# PocketKerbal.net
KiCad netlist of a schematic drawn in EAGLE
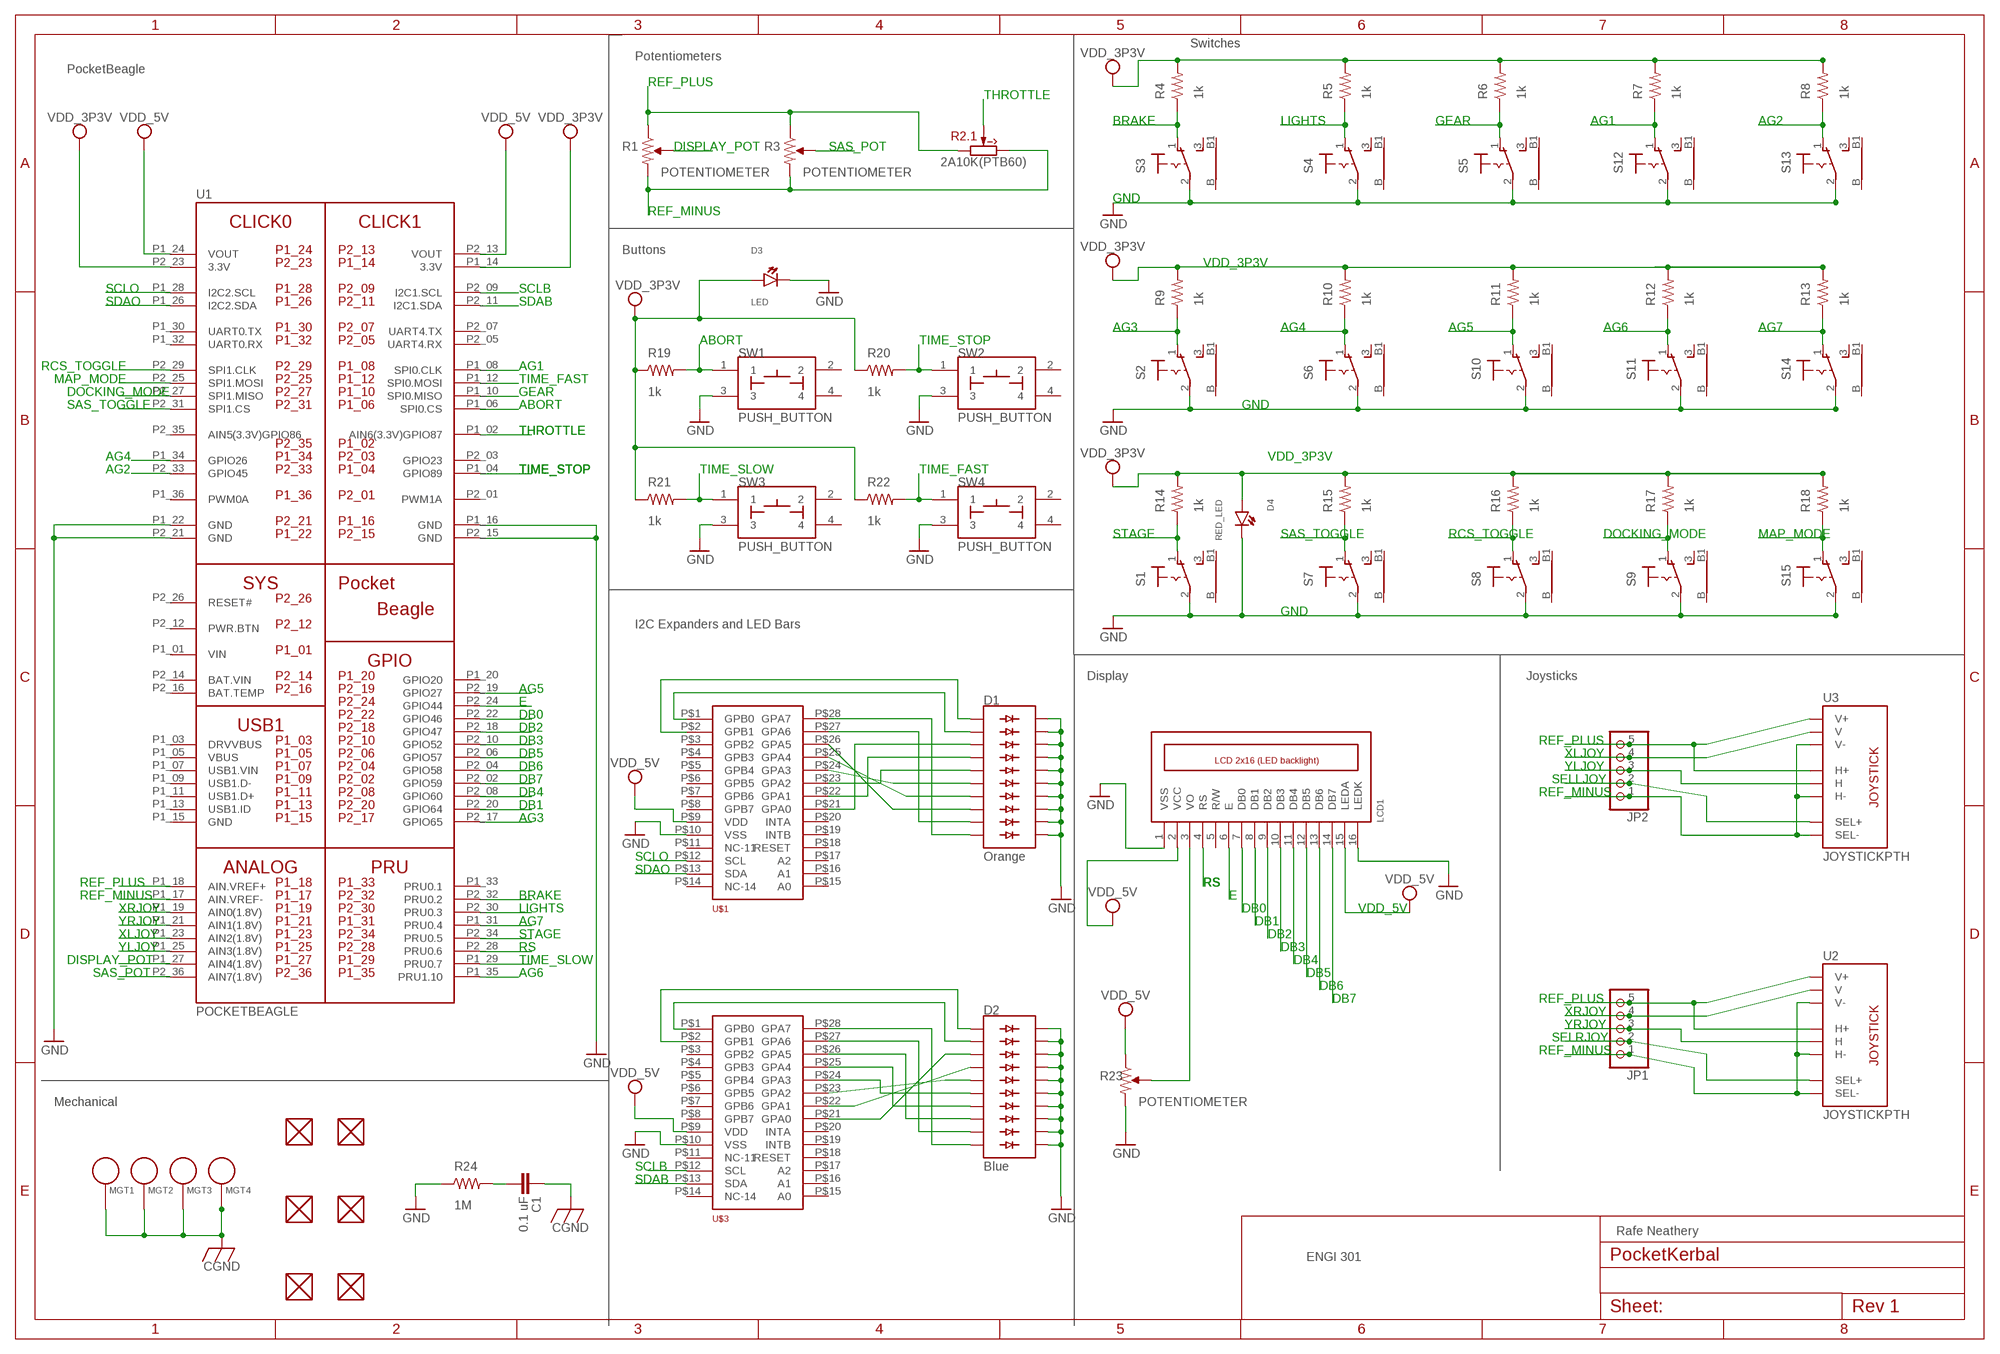
[diagram p0: schematic, sheet 1]

(export (version "E")
  (design (tool "Eeschema 10.0.6"))
  (components
    (comp (ref "C1")
      (value "0.1 uF")
      (footprint "eagle-import:C0402")
      (libsource (lib "eagle-import") (part "C_C0402"))
    )
    (comp (ref "D1")
      (value "RED")
      (footprint "eagle-import:LED_BARGRAPH_10")
      (libsource (lib "eagle-import") (part "LED_BARGRAPH_10RED"))
    )
    (comp (ref "D2")
      (value "RED")
      (footprint "eagle-import:LED_BARGRAPH_10")
      (libsource (lib "eagle-import") (part "LED_BARGRAPH_10RED"))
    )
    (comp (ref "D3")
      (value "LED")
      (footprint "eagle-import:EIA-STD")
      (libsource (lib "eagle-import") (part "LED"))
    )
    (comp (ref "D4")
      (value "RED_LED")
      (footprint "eagle-import:EIA-STD")
      (libsource (lib "eagle-import") (part "LED"))
    )
    (comp (ref "FUD1")
      (value "FIDUCIAL")
      (footprint "eagle-import:FIDUCIAL_40MIL")
      (libsource (lib "eagle-import") (part "FIDUCIAL"))
    )
    (comp (ref "FUD2")
      (value "FIDUCIAL")
      (footprint "eagle-import:FIDUCIAL_40MIL")
      (libsource (lib "eagle-import") (part "FIDUCIAL"))
    )
    (comp (ref "FUD5")
      (value "FIDUCIAL")
      (footprint "eagle-import:FIDUCIAL_40MIL")
      (libsource (lib "eagle-import") (part "FIDUCIAL"))
    )
    (comp (ref "FUD6")
      (value "FIDUCIAL")
      (footprint "eagle-import:FIDUCIAL_40MIL")
      (libsource (lib "eagle-import") (part "FIDUCIAL"))
    )
    (comp (ref "FUD9")
      (value "FIDUCIAL")
      (footprint "eagle-import:FIDUCIAL_40MIL")
      (libsource (lib "eagle-import") (part "FIDUCIAL"))
    )
    (comp (ref "FUD10")
      (value "FIDUCIAL")
      (footprint "eagle-import:FIDUCIAL_40MIL")
      (libsource (lib "eagle-import") (part "FIDUCIAL"))
    )
    (comp (ref "JP1")
      (value "PINHD-1X5")
      (footprint "eagle-import:1X05")
      (libsource (lib "eagle-import") (part "PINHD-1X5"))
    )
    (comp (ref "JP2")
      (value "PINHD-1X5")
      (footprint "eagle-import:1X05")
      (libsource (lib "eagle-import") (part "PINHD-1X5"))
    )
    (comp (ref "LCD1")
      (value "LCD_2X16_SIL")
      (footprint "eagle-import:HY-1602F")
      (libsource (lib "eagle-import") (part "LCD_2X16_SIL"))
    )
    (comp (ref "MGT1")
      (value "MOUNTING_HOLE")
      (footprint "eagle-import:MOUNTING_HOLE")
      (libsource (lib "eagle-import") (part "MOUNTING_HOLE"))
    )
    (comp (ref "MGT2")
      (value "MOUNTING_HOLE")
      (footprint "eagle-import:MOUNTING_HOLE")
      (libsource (lib "eagle-import") (part "MOUNTING_HOLE"))
    )
    (comp (ref "MGT3")
      (value "MOUNTING_HOLE")
      (footprint "eagle-import:MOUNTING_HOLE")
      (libsource (lib "eagle-import") (part "MOUNTING_HOLE"))
    )
    (comp (ref "MGT4")
      (value "MOUNTING_HOLE")
      (footprint "eagle-import:MOUNTING_HOLE")
      (libsource (lib "eagle-import") (part "MOUNTING_HOLE"))
    )
    (comp (ref "R1")
      (value "POTENTIOMETER")
      (footprint "eagle-import:POT-PO90S")
      (libsource (lib "eagle-import") (part "POTENTIOMETER"))
    )
    (comp (ref "R2")
      (value "2A10K(PTB60)")
      (footprint "eagle-import:PTB6044")
      (libsource (lib "eagle-import") (part "2?(PTB60)A10K"))
    )
    (comp (ref "R3")
      (value "POTENTIOMETER")
      (footprint "eagle-import:POT-PO90S")
      (libsource (lib "eagle-import") (part "POTENTIOMETER"))
    )
    (comp (ref "R4")
      (value "1k")
      (footprint "eagle-import:R0603")
      (libsource (lib "eagle-import") (part "R_R0603"))
    )
    (comp (ref "R5")
      (value "1k")
      (footprint "eagle-import:R0603")
      (libsource (lib "eagle-import") (part "R_R0603"))
    )
    (comp (ref "R6")
      (value "1k")
      (footprint "eagle-import:R0603")
      (libsource (lib "eagle-import") (part "R_R0603"))
    )
    (comp (ref "R7")
      (value "1k")
      (footprint "eagle-import:R0603")
      (libsource (lib "eagle-import") (part "R_R0603"))
    )
    (comp (ref "R8")
      (value "1k")
      (footprint "eagle-import:R0603")
      (libsource (lib "eagle-import") (part "R_R0603"))
    )
    (comp (ref "R9")
      (value "1k")
      (footprint "eagle-import:R0603")
      (libsource (lib "eagle-import") (part "R_R0603"))
    )
    (comp (ref "R10")
      (value "1k")
      (footprint "eagle-import:R0603")
      (libsource (lib "eagle-import") (part "R_R0603"))
    )
    (comp (ref "R11")
      (value "1k")
      (footprint "eagle-import:R0603")
      (libsource (lib "eagle-import") (part "R_R0603"))
    )
    (comp (ref "R12")
      (value "1k")
      (footprint "eagle-import:R0603")
      (libsource (lib "eagle-import") (part "R_R0603"))
    )
    (comp (ref "R13")
      (value "1k")
      (footprint "eagle-import:R0603")
      (libsource (lib "eagle-import") (part "R_R0603"))
    )
    (comp (ref "R14")
      (value "1k")
      (footprint "eagle-import:R0603")
      (libsource (lib "eagle-import") (part "R_R0603"))
    )
    (comp (ref "R15")
      (value "1k")
      (footprint "eagle-import:R0603")
      (libsource (lib "eagle-import") (part "R_R0603"))
    )
    (comp (ref "R16")
      (value "1k")
      (footprint "eagle-import:R0603")
      (libsource (lib "eagle-import") (part "R_R0603"))
    )
    (comp (ref "R17")
      (value "1k")
      (footprint "eagle-import:R0603")
      (libsource (lib "eagle-import") (part "R_R0603"))
    )
    (comp (ref "R18")
      (value "1k")
      (footprint "eagle-import:R0603")
      (libsource (lib "eagle-import") (part "R_R0603"))
    )
    (comp (ref "R19")
      (value "1k")
      (footprint "eagle-import:R0603")
      (libsource (lib "eagle-import") (part "R_R0603"))
    )
    (comp (ref "R20")
      (value "1k")
      (footprint "eagle-import:R0603")
      (libsource (lib "eagle-import") (part "R_R0603"))
    )
    (comp (ref "R21")
      (value "1k")
      (footprint "eagle-import:R0603")
      (libsource (lib "eagle-import") (part "R_R0603"))
    )
    (comp (ref "R22")
      (value "1k")
      (footprint "eagle-import:R0603")
      (libsource (lib "eagle-import") (part "R_R0603"))
    )
    (comp (ref "R23")
      (value "POTENTIOMETER")
      (footprint "eagle-import:POT-PO90S")
      (libsource (lib "eagle-import") (part "POTENTIOMETER"))
    )
    (comp (ref "R24")
      (value "1M")
      (footprint "eagle-import:R0603")
      (libsource (lib "eagle-import") (part "R_R0603"))
    )
    (comp (ref "S1")
      (value "9070-1W")
      (footprint "eagle-import:9070-1W")
      (libsource (lib "eagle-import") (part "9070-1W"))
    )
    (comp (ref "S2")
      (value "9070-1W")
      (footprint "eagle-import:9070-1W")
      (libsource (lib "eagle-import") (part "9070-1W"))
    )
    (comp (ref "S3")
      (value "9070-1W")
      (footprint "eagle-import:9070-1W")
      (libsource (lib "eagle-import") (part "9070-1W"))
    )
    (comp (ref "S4")
      (value "9070-1W")
      (footprint "eagle-import:9070-1W")
      (libsource (lib "eagle-import") (part "9070-1W"))
    )
    (comp (ref "S5")
      (value "9070-1W")
      (footprint "eagle-import:9070-1W")
      (libsource (lib "eagle-import") (part "9070-1W"))
    )
    (comp (ref "S6")
      (value "9070-1W")
      (footprint "eagle-import:9070-1W")
      (libsource (lib "eagle-import") (part "9070-1W"))
    )
    (comp (ref "S7")
      (value "9070-1W")
      (footprint "eagle-import:9070-1W")
      (libsource (lib "eagle-import") (part "9070-1W"))
    )
    (comp (ref "S8")
      (value "9070-1W")
      (footprint "eagle-import:9070-1W")
      (libsource (lib "eagle-import") (part "9070-1W"))
    )
    (comp (ref "S9")
      (value "9070-1W")
      (footprint "eagle-import:9070-1W")
      (libsource (lib "eagle-import") (part "9070-1W"))
    )
    (comp (ref "S10")
      (value "9070-1W")
      (footprint "eagle-import:9070-1W")
      (libsource (lib "eagle-import") (part "9070-1W"))
    )
    (comp (ref "S11")
      (value "9070-1W")
      (footprint "eagle-import:9070-1W")
      (libsource (lib "eagle-import") (part "9070-1W"))
    )
    (comp (ref "S12")
      (value "9070-1W")
      (footprint "eagle-import:9070-1W")
      (libsource (lib "eagle-import") (part "9070-1W"))
    )
    (comp (ref "S13")
      (value "9070-1W")
      (footprint "eagle-import:9070-1W")
      (libsource (lib "eagle-import") (part "9070-1W"))
    )
    (comp (ref "S14")
      (value "9070-1W")
      (footprint "eagle-import:9070-1W")
      (libsource (lib "eagle-import") (part "9070-1W"))
    )
    (comp (ref "S15")
      (value "9070-1W")
      (footprint "eagle-import:9070-1W")
      (libsource (lib "eagle-import") (part "9070-1W"))
    )
    (comp (ref "SW1")
      (value "PUSH_BUTTON")
      (footprint "eagle-import:BUTTON_12.5MM")
      (libsource (lib "eagle-import") (part "PUSH_BUTTON"))
    )
    (comp (ref "SW2")
      (value "PUSH_BUTTON")
      (footprint "eagle-import:BUTTON_12.5MM")
      (libsource (lib "eagle-import") (part "PUSH_BUTTON"))
    )
    (comp (ref "SW3")
      (value "PUSH_BUTTON")
      (footprint "eagle-import:BUTTON_12.5MM")
      (libsource (lib "eagle-import") (part "PUSH_BUTTON"))
    )
    (comp (ref "SW4")
      (value "PUSH_BUTTON")
      (footprint "eagle-import:BUTTON_12.5MM")
      (libsource (lib "eagle-import") (part "PUSH_BUTTON"))
    )
    (comp (ref "U$1")
      (value "MCP23017-E/SP")
      (footprint "eagle-import:DIP28")
      (libsource (lib "eagle-import") (part "MCP23017-E/SP"))
    )
    (comp (ref "U$3")
      (value "MCP23017-E/SP")
      (footprint "eagle-import:DIP28")
      (libsource (lib "eagle-import") (part "MCP23017-E/SP"))
    )
    (comp (ref "U1")
      (value "POCKETBEAGLE")
      (footprint "eagle-import:POCKETBEAGLE")
      (libsource (lib "eagle-import") (part "POCKETBEAGLE"))
    )
    (comp (ref "U2")
      (value "JOYSTICKPTH")
      (footprint "eagle-import:JOYSTICK")
      (libsource (lib "eagle-import") (part "JOYSTICKPTH"))
    )
    (comp (ref "U3")
      (value "JOYSTICKPTH")
      (footprint "eagle-import:JOYSTICK")
      (libsource (lib "eagle-import") (part "JOYSTICKPTH"))
    )
  )
  (nets
    (net (code "1") (name "/ABORT") (class "Default")
      (node (ref "R19") (pin "2") (pinfunction "2_2") (pintype "passive"))
      (node (ref "SW1") (pin "1") (pinfunction "1_1") (pintype "bidirectional"))
      (node (ref "U1") (pin "P1_06") (pinfunction "SPI0.CS_P1_06") (pintype "bidirectional"))
    )
    (net (code "2") (name "/AG1") (class "Default")
      (node (ref "R7") (pin "1") (pinfunction "1_1") (pintype "passive"))
      (node (ref "S12") (pin "1") (pinfunction "O_1") (pintype "passive"))
      (node (ref "U1") (pin "P1_08") (pinfunction "SPI0.CLK_P1_08") (pintype "bidirectional"))
    )
    (net (code "3") (name "/AG2") (class "Default")
      (node (ref "R8") (pin "1") (pinfunction "1_1") (pintype "passive"))
      (node (ref "S13") (pin "1") (pinfunction "O_1") (pintype "passive"))
      (node (ref "U1") (pin "P2_33") (pinfunction "GPIO45_P2_33") (pintype "bidirectional"))
    )
    (net (code "4") (name "/AG3") (class "Default")
      (node (ref "R9") (pin "1") (pinfunction "1_1") (pintype "passive"))
      (node (ref "S2") (pin "1") (pinfunction "O_1") (pintype "passive"))
      (node (ref "U1") (pin "P2_17") (pinfunction "GPIO65_P2_17") (pintype "bidirectional"))
    )
    (net (code "5") (name "/AG4") (class "Default")
      (node (ref "R10") (pin "1") (pinfunction "1_1") (pintype "passive"))
      (node (ref "S6") (pin "1") (pinfunction "O_1") (pintype "passive"))
      (node (ref "U1") (pin "P1_34") (pinfunction "GPIO26_P1_34") (pintype "bidirectional"))
    )
    (net (code "6") (name "/AG5") (class "Default")
      (node (ref "R11") (pin "1") (pinfunction "1_1") (pintype "passive"))
      (node (ref "S10") (pin "1") (pinfunction "O_1") (pintype "passive"))
      (node (ref "U1") (pin "P2_19") (pinfunction "GPIO27_P2_19") (pintype "bidirectional"))
    )
    (net (code "7") (name "/AG6") (class "Default")
      (node (ref "R12") (pin "1") (pinfunction "1_1") (pintype "passive"))
      (node (ref "S11") (pin "1") (pinfunction "O_1") (pintype "passive"))
      (node (ref "U1") (pin "P1_35") (pinfunction "PRU1.10_P1_35") (pintype "bidirectional"))
    )
    (net (code "8") (name "/AG7") (class "Default")
      (node (ref "R13") (pin "1") (pinfunction "1_1") (pintype "passive"))
      (node (ref "S14") (pin "1") (pinfunction "O_1") (pintype "passive"))
      (node (ref "U1") (pin "P1_31") (pinfunction "PRU0.4_P1_31") (pintype "bidirectional"))
    )
    (net (code "9") (name "/BAT.VIN") (class "Default")
      (node (ref "U1") (pin "P2_14") (pinfunction "BAT.VIN_P2_14") (pintype "power_in"))
    )
    (net (code "10") (name "/BRAKE") (class "Default")
      (node (ref "R4") (pin "1") (pinfunction "1_1") (pintype "passive"))
      (node (ref "S3") (pin "1") (pinfunction "O_1") (pintype "passive"))
      (node (ref "U1") (pin "P2_32") (pinfunction "PRU0.2_P2_32") (pintype "bidirectional"))
    )
    (net (code "11") (name "/DB0") (class "Default")
      (node (ref "LCD1") (pin "7") (pinfunction "DB0_7") (pintype "bidirectional"))
      (node (ref "U1") (pin "P2_22") (pinfunction "GPIO46_P2_22") (pintype "bidirectional"))
    )
    (net (code "12") (name "/DB1") (class "Default")
      (node (ref "LCD1") (pin "8") (pinfunction "DB1_8") (pintype "bidirectional"))
      (node (ref "U1") (pin "P2_20") (pinfunction "GPIO64_P2_20") (pintype "bidirectional"))
    )
    (net (code "13") (name "/DB2") (class "Default")
      (node (ref "LCD1") (pin "9") (pinfunction "DB2_9") (pintype "bidirectional"))
      (node (ref "U1") (pin "P2_18") (pinfunction "GPIO47_P2_18") (pintype "bidirectional"))
    )
    (net (code "14") (name "/DB3") (class "Default")
      (node (ref "LCD1") (pin "10") (pinfunction "DB3_10") (pintype "bidirectional"))
      (node (ref "U1") (pin "P2_10") (pinfunction "GPIO52_P2_10") (pintype "bidirectional"))
    )
    (net (code "15") (name "/DB4") (class "Default")
      (node (ref "LCD1") (pin "11") (pinfunction "DB4_11") (pintype "bidirectional"))
      (node (ref "U1") (pin "P2_08") (pinfunction "GPIO60_P2_08") (pintype "bidirectional"))
    )
    (net (code "16") (name "/DB5") (class "Default")
      (node (ref "LCD1") (pin "12") (pinfunction "DB5_12") (pintype "bidirectional"))
      (node (ref "U1") (pin "P2_06") (pinfunction "GPIO57_P2_06") (pintype "bidirectional"))
    )
    (net (code "17") (name "/DB6") (class "Default")
      (node (ref "LCD1") (pin "13") (pinfunction "DB6_13") (pintype "bidirectional"))
      (node (ref "U1") (pin "P2_04") (pinfunction "GPIO58_P2_04") (pintype "bidirectional"))
    )
    (net (code "18") (name "/DB7") (class "Default")
      (node (ref "LCD1") (pin "14") (pinfunction "DB7_14") (pintype "bidirectional"))
      (node (ref "U1") (pin "P2_02") (pinfunction "GPIO59_P2_02") (pintype "bidirectional"))
    )
    (net (code "19") (name "/DISPLAY_POT") (class "Default")
      (node (ref "R1") (pin "S") (pinfunction "S_S") (pintype "bidirectional"))
      (node (ref "U1") (pin "P1_27") (pinfunction "AIN4(1.8V)_P1_27") (pintype "input"))
    )
    (net (code "20") (name "/DOCKING_MODE") (class "Default")
      (node (ref "R17") (pin "1") (pinfunction "1_1") (pintype "passive"))
      (node (ref "S9") (pin "1") (pinfunction "O_1") (pintype "passive"))
      (node (ref "U1") (pin "P2_27") (pinfunction "SPI1.MISO_P2_27") (pintype "bidirectional"))
    )
    (net (code "21") (name "/E") (class "Default")
      (node (ref "LCD1") (pin "6") (pinfunction "E_6") (pintype "input"))
      (node (ref "U1") (pin "P2_24") (pinfunction "GPIO44_P2_24") (pintype "bidirectional"))
    )
    (net (code "22") (name "/GEAR") (class "Default")
      (node (ref "R6") (pin "1") (pinfunction "1_1") (pintype "passive"))
      (node (ref "S5") (pin "1") (pinfunction "O_1") (pintype "passive"))
      (node (ref "U1") (pin "P1_10") (pinfunction "SPI0.MISO_P1_10") (pintype "bidirectional"))
    )
    (net (code "23") (name "/LIGHTS") (class "Default")
      (node (ref "R5") (pin "1") (pinfunction "1_1") (pintype "passive"))
      (node (ref "S4") (pin "1") (pinfunction "O_1") (pintype "passive"))
      (node (ref "U1") (pin "P2_30") (pinfunction "PRU0.3_P2_30") (pintype "bidirectional"))
    )
    (net (code "24") (name "/MAP_MODE") (class "Default")
      (node (ref "R18") (pin "1") (pinfunction "1_1") (pintype "passive"))
      (node (ref "S15") (pin "1") (pinfunction "O_1") (pintype "passive"))
      (node (ref "U1") (pin "P2_25") (pinfunction "SPI1.MOSI_P2_25") (pintype "bidirectional"))
    )
    (net (code "25") (name "/RCS_TOGGLE") (class "Default")
      (node (ref "R16") (pin "1") (pinfunction "1_1") (pintype "passive"))
      (node (ref "S8") (pin "1") (pinfunction "O_1") (pintype "passive"))
      (node (ref "U1") (pin "P2_29") (pinfunction "SPI1.CLK_P2_29") (pintype "bidirectional"))
    )
    (net (code "26") (name "/REF_MINUS") (class "Default")
      (node (ref "JP1") (pin "1") (pinfunction "1_1") (pintype "passive"))
      (node (ref "JP2") (pin "1") (pinfunction "1_1") (pintype "passive"))
      (node (ref "R1") (pin "CW") (pinfunction "CW_CW") (pintype "passive"))
      (node (ref "R2") (pin "A3") (pinfunction "CW_A3") (pintype "passive"))
      (node (ref "R3") (pin "CW") (pinfunction "CW_CW") (pintype "passive"))
      (node (ref "U1") (pin "P1_17") (pinfunction "AIN.VREF-_P1_17") (pintype "input"))
      (node (ref "U2") (pin "B2A") (pinfunction "SEL-_B2A") (pintype "bidirectional"))
      (node (ref "U2") (pin "H3") (pinfunction "H-_H3") (pintype "bidirectional"))
      (node (ref "U2") (pin "V3") (pinfunction "V-_V3") (pintype "bidirectional"))
      (node (ref "U3") (pin "B2A") (pinfunction "SEL-_B2A") (pintype "bidirectional"))
      (node (ref "U3") (pin "H3") (pinfunction "H-_H3") (pintype "bidirectional"))
      (node (ref "U3") (pin "V3") (pinfunction "V-_V3") (pintype "bidirectional"))
    )
    (net (code "27") (name "/REF_PLUS") (class "Default")
      (node (ref "JP1") (pin "5") (pinfunction "5_5") (pintype "passive"))
      (node (ref "JP2") (pin "5") (pinfunction "5_5") (pintype "passive"))
      (node (ref "R1") (pin "CCW") (pinfunction "CCW_CCW") (pintype "passive"))
      (node (ref "R2") (pin "A1") (pinfunction "CCW_A1") (pintype "passive"))
      (node (ref "R3") (pin "CCW") (pinfunction "CCW_CCW") (pintype "passive"))
      (node (ref "U1") (pin "P1_18") (pinfunction "AIN.VREF+_P1_18") (pintype "input"))
      (node (ref "U2") (pin "H1") (pinfunction "H+_H1") (pintype "bidirectional"))
      (node (ref "U2") (pin "V1") (pinfunction "V+_V1") (pintype "bidirectional"))
      (node (ref "U3") (pin "H1") (pinfunction "H+_H1") (pintype "bidirectional"))
      (node (ref "U3") (pin "V1") (pinfunction "V+_V1") (pintype "bidirectional"))
    )
    (net (code "28") (name "/RS") (class "Default")
      (node (ref "LCD1") (pin "4") (pinfunction "RS_4") (pintype "input"))
      (node (ref "U1") (pin "P2_28") (pinfunction "PRU0.6_P2_28") (pintype "bidirectional"))
    )
    (net (code "29") (name "/SAS_POT") (class "Default")
      (node (ref "R3") (pin "S") (pinfunction "S_S") (pintype "bidirectional"))
      (node (ref "U1") (pin "P2_36") (pinfunction "AIN7(1.8V)_P2_36") (pintype "input"))
    )
    (net (code "30") (name "/SAS_TOGGLE") (class "Default")
      (node (ref "R15") (pin "1") (pinfunction "1_1") (pintype "passive"))
      (node (ref "S7") (pin "1") (pinfunction "O_1") (pintype "passive"))
      (node (ref "U1") (pin "P2_31") (pinfunction "SPI1.CS_P2_31") (pintype "bidirectional"))
    )
    (net (code "31") (name "/SCLB") (class "Default")
      (node (ref "U$3") (pin "P$12") (pinfunction "SCL_P$12") (pintype "bidirectional"))
      (node (ref "U1") (pin "P2_09") (pinfunction "I2C1.SCL_P2_09") (pintype "bidirectional"))
    )
    (net (code "32") (name "/SCLO") (class "Default")
      (node (ref "U$1") (pin "P$12") (pinfunction "SCL_P$12") (pintype "bidirectional"))
      (node (ref "U1") (pin "P1_28") (pinfunction "I2C2.SCL_P1_28") (pintype "bidirectional"))
    )
    (net (code "33") (name "/SDAB") (class "Default")
      (node (ref "U$3") (pin "P$13") (pinfunction "SDA_P$13") (pintype "bidirectional"))
      (node (ref "U1") (pin "P2_11") (pinfunction "I2C1.SDA_P2_11") (pintype "bidirectional"))
    )
    (net (code "34") (name "/SDAO") (class "Default")
      (node (ref "U$1") (pin "P$13") (pinfunction "SDA_P$13") (pintype "bidirectional"))
      (node (ref "U1") (pin "P1_26") (pinfunction "I2C2.SDA_P1_26") (pintype "bidirectional"))
    )
    (net (code "35") (name "/SELLJOY") (class "Default")
      (node (ref "JP2") (pin "2") (pinfunction "2_2") (pintype "passive"))
      (node (ref "U3") (pin "B1A") (pinfunction "SEL+_B1A") (pintype "bidirectional"))
    )
    (net (code "36") (name "/SELRJOY") (class "Default")
      (node (ref "JP1") (pin "2") (pinfunction "2_2") (pintype "passive"))
      (node (ref "U2") (pin "B1A") (pinfunction "SEL+_B1A") (pintype "bidirectional"))
    )
    (net (code "37") (name "/STAGE") (class "Default")
      (node (ref "R14") (pin "1") (pinfunction "1_1") (pintype "passive"))
      (node (ref "S1") (pin "1") (pinfunction "O_1") (pintype "passive"))
      (node (ref "U1") (pin "P2_34") (pinfunction "PRU0.5_P2_34") (pintype "bidirectional"))
    )
    (net (code "38") (name "/THROTTLE") (class "Default")
      (node (ref "R2") (pin "A2") (pinfunction "W_A2") (pintype "passive"))
      (node (ref "U1") (pin "P1_02") (pinfunction "AIN6(3.3V)GPIO87_P1_02") (pintype "bidirectional"))
    )
    (net (code "39") (name "/TIME_FAST") (class "Default")
      (node (ref "R22") (pin "2") (pinfunction "2_2") (pintype "passive"))
      (node (ref "SW4") (pin "1") (pinfunction "1_1") (pintype "bidirectional"))
      (node (ref "U1") (pin "P1_12") (pinfunction "SPI0.MOSI_P1_12") (pintype "bidirectional"))
    )
    (net (code "40") (name "/TIME_SLOW") (class "Default")
      (node (ref "R21") (pin "2") (pinfunction "2_2") (pintype "passive"))
      (node (ref "SW3") (pin "1") (pinfunction "1_1") (pintype "bidirectional"))
      (node (ref "U1") (pin "P1_29") (pinfunction "PRU0.7_P1_29") (pintype "bidirectional"))
    )
    (net (code "41") (name "/TIME_STOP") (class "Default")
      (node (ref "R20") (pin "2") (pinfunction "2_2") (pintype "passive"))
      (node (ref "SW2") (pin "1") (pinfunction "1_1") (pintype "bidirectional"))
      (node (ref "U1") (pin "P1_04") (pinfunction "GPIO89_P1_04") (pintype "bidirectional"))
    )
    (net (code "42") (name "/VIN") (class "Default")
      (node (ref "U1") (pin "P1_01") (pinfunction "VIN_P1_01") (pintype "power_in"))
    )
    (net (code "43") (name "/XLJOY") (class "Default")
      (node (ref "JP2") (pin "4") (pinfunction "4_4") (pintype "passive"))
      (node (ref "U1") (pin "P1_23") (pinfunction "AIN2(1.8V)_P1_23") (pintype "input"))
      (node (ref "U3") (pin "V2") (pinfunction "V_V2") (pintype "bidirectional"))
    )
    (net (code "44") (name "/XRJOY") (class "Default")
      (node (ref "JP1") (pin "4") (pinfunction "4_4") (pintype "passive"))
      (node (ref "U1") (pin "P1_19") (pinfunction "AIN0(1.8V)_P1_19") (pintype "input"))
      (node (ref "U2") (pin "V2") (pinfunction "V_V2") (pintype "bidirectional"))
    )
    (net (code "45") (name "/YLJOY") (class "Default")
      (node (ref "JP2") (pin "3") (pinfunction "3_3") (pintype "passive"))
      (node (ref "U1") (pin "P1_25") (pinfunction "AIN3(1.8V)_P1_25") (pintype "input"))
      (node (ref "U3") (pin "H2") (pinfunction "H_H2") (pintype "bidirectional"))
    )
    (net (code "46") (name "/YRJOY") (class "Default")
      (node (ref "JP1") (pin "3") (pinfunction "3_3") (pintype "passive"))
      (node (ref "U1") (pin "P1_21") (pinfunction "AIN1(1.8V)_P1_21") (pintype "input"))
      (node (ref "U2") (pin "H2") (pinfunction "H_H2") (pintype "bidirectional"))
    )
    (net (code "47") (name "CGND") (class "Default")
      (node (ref "C1") (pin "1") (pinfunction "1_1") (pintype "passive"))
      (node (ref "MGT1") (pin "P$1") (pinfunction "P$1_P$1") (pintype "bidirectional"))
      (node (ref "MGT2") (pin "P$1") (pinfunction "P$1_P$1") (pintype "bidirectional"))
      (node (ref "MGT3") (pin "P$1") (pinfunction "P$1_P$1") (pintype "bidirectional"))
      (node (ref "MGT4") (pin "P$1") (pinfunction "P$1_P$1") (pintype "bidirectional"))
    )
    (net (code "48") (name "GND") (class "Default")
      (node (ref "D1") (pin "11") (pinfunction "C9_11") (pintype "passive"))
      (node (ref "D1") (pin "12") (pinfunction "C8_12") (pintype "passive"))
      (node (ref "D1") (pin "13") (pinfunction "C7_13") (pintype "passive"))
      (node (ref "D1") (pin "14") (pinfunction "C6_14") (pintype "passive"))
      (node (ref "D1") (pin "15") (pinfunction "C5_15") (pintype "passive"))
      (node (ref "D1") (pin "16") (pinfunction "C4_16") (pintype "passive"))
      (node (ref "D1") (pin "17") (pinfunction "C3_17") (pintype "passive"))
      (node (ref "D1") (pin "18") (pinfunction "C2_18") (pintype "passive"))
      (node (ref "D1") (pin "19") (pinfunction "C1_19") (pintype "passive"))
      (node (ref "D1") (pin "20") (pinfunction "C_20") (pintype "passive"))
      (node (ref "D2") (pin "11") (pinfunction "C9_11") (pintype "passive"))
      (node (ref "D2") (pin "12") (pinfunction "C8_12") (pintype "passive"))
      (node (ref "D2") (pin "13") (pinfunction "C7_13") (pintype "passive"))
      (node (ref "D2") (pin "14") (pinfunction "C6_14") (pintype "passive"))
      (node (ref "D2") (pin "15") (pinfunction "C5_15") (pintype "passive"))
      (node (ref "D2") (pin "16") (pinfunction "C4_16") (pintype "passive"))
      (node (ref "D2") (pin "17") (pinfunction "C3_17") (pintype "passive"))
      (node (ref "D2") (pin "18") (pinfunction "C2_18") (pintype "passive"))
      (node (ref "D2") (pin "19") (pinfunction "C1_19") (pintype "passive"))
      (node (ref "D2") (pin "20") (pinfunction "C_20") (pintype "passive"))
      (node (ref "D3") (pin "CATHODE") (pinfunction "CATHODE_CATHODE") (pintype "bidirectional"))
      (node (ref "D4") (pin "CATHODE") (pinfunction "CATHODE_CATHODE") (pintype "bidirectional"))
      (node (ref "LCD1") (pin "1") (pinfunction "VSS_1") (pintype "power_in"))
      (node (ref "LCD1") (pin "16") (pinfunction "LEDK_16") (pintype "passive"))
      (node (ref "R23") (pin "CW") (pinfunction "CW_CW") (pintype "passive"))
      (node (ref "R24") (pin "1") (pinfunction "1_1") (pintype "passive"))
      (node (ref "S1") (pin "2") (pinfunction "P_2") (pintype "passive"))
      (node (ref "S10") (pin "2") (pinfunction "P_2") (pintype "passive"))
      (node (ref "S11") (pin "2") (pinfunction "P_2") (pintype "passive"))
      (node (ref "S12") (pin "2") (pinfunction "P_2") (pintype "passive"))
      (node (ref "S13") (pin "2") (pinfunction "P_2") (pintype "passive"))
      (node (ref "S14") (pin "2") (pinfunction "P_2") (pintype "passive"))
      (node (ref "S15") (pin "2") (pinfunction "P_2") (pintype "passive"))
      (node (ref "S2") (pin "2") (pinfunction "P_2") (pintype "passive"))
      (node (ref "S3") (pin "2") (pinfunction "P_2") (pintype "passive"))
      (node (ref "S4") (pin "2") (pinfunction "P_2") (pintype "passive"))
      (node (ref "S5") (pin "2") (pinfunction "P_2") (pintype "passive"))
      (node (ref "S6") (pin "2") (pinfunction "P_2") (pintype "passive"))
      (node (ref "S7") (pin "2") (pinfunction "P_2") (pintype "passive"))
      (node (ref "S8") (pin "2") (pinfunction "P_2") (pintype "passive"))
      (node (ref "S9") (pin "2") (pinfunction "P_2") (pintype "passive"))
      (node (ref "SW1") (pin "3") (pinfunction "3_3") (pintype "bidirectional"))
      (node (ref "SW2") (pin "3") (pinfunction "3_3") (pintype "bidirectional"))
      (node (ref "SW3") (pin "3") (pinfunction "3_3") (pintype "bidirectional"))
      (node (ref "SW4") (pin "3") (pinfunction "3_3") (pintype "bidirectional"))
      (node (ref "U$1") (pin "P$10") (pinfunction "VSS_P$10") (pintype "bidirectional"))
      (node (ref "U$3") (pin "P$10") (pinfunction "VSS_P$10") (pintype "bidirectional"))
      (node (ref "U1") (pin "P1_16") (pinfunction "GND_P1_16") (pintype "power_in"))
      (node (ref "U1") (pin "P1_22") (pinfunction "GND_P1_22") (pintype "power_in"))
      (node (ref "U1") (pin "P2_15") (pinfunction "GND_P2_15") (pintype "power_in"))
      (node (ref "U1") (pin "P2_21") (pinfunction "GND_P2_21") (pintype "power_in"))
    )
    (net (code "49") (name "Net-(C1-Pad2)") (class "Default")
      (node (ref "C1") (pin "2") (pinfunction "2_2") (pintype "passive"))
      (node (ref "R24") (pin "2") (pinfunction "2_2") (pintype "passive"))
    )
    (net (code "50") (name "Net-(D1-A)") (class "Default")
      (node (ref "D1") (pin "1") (pinfunction "A_1") (pintype "passive"))
      (node (ref "U$1") (pin "P$2") (pinfunction "GPB1_P$2") (pintype "bidirectional"))
    )
    (net (code "51") (name "Net-(D1-A1)") (class "Default")
      (node (ref "D1") (pin "2") (pinfunction "A1_2") (pintype "passive"))
      (node (ref "U$1") (pin "P$1") (pinfunction "GPB0_P$1") (pintype "bidirectional"))
    )
    (net (code "52") (name "Net-(D1-A2)") (class "Default")
      (node (ref "D1") (pin "3") (pinfunction "A2_3") (pintype "passive"))
      (node (ref "U$1") (pin "P$21") (pinfunction "GPA0_P$21") (pintype "bidirectional"))
    )
    (net (code "53") (name "Net-(D1-A3)") (class "Default")
      (node (ref "D1") (pin "4") (pinfunction "A3_4") (pintype "passive"))
      (node (ref "U$1") (pin "P$22") (pinfunction "GPA1_P$22") (pintype "bidirectional"))
    )
    (net (code "54") (name "Net-(D1-A4)") (class "Default")
      (node (ref "D1") (pin "5") (pinfunction "A4_5") (pintype "passive"))
      (node (ref "U$1") (pin "P$23") (pinfunction "GPA2_P$23") (pintype "bidirectional"))
    )
    (net (code "55") (name "Net-(D1-A5)") (class "Default")
      (node (ref "D1") (pin "6") (pinfunction "A5_6") (pintype "passive"))
      (node (ref "U$1") (pin "P$24") (pinfunction "GPA3_P$24") (pintype "bidirectional"))
    )
    (net (code "56") (name "Net-(D1-A6)") (class "Default")
      (node (ref "D1") (pin "7") (pinfunction "A6_7") (pintype "passive"))
      (node (ref "U$1") (pin "P$25") (pinfunction "GPA4_P$25") (pintype "bidirectional"))
    )
    (net (code "57") (name "Net-(D1-A7)") (class "Default")
      (node (ref "D1") (pin "8") (pinfunction "A7_8") (pintype "passive"))
      (node (ref "U$1") (pin "P$26") (pinfunction "GPA5_P$26") (pintype "bidirectional"))
    )
    (net (code "58") (name "Net-(D1-A8)") (class "Default")
      (node (ref "D1") (pin "9") (pinfunction "A8_9") (pintype "passive"))
      (node (ref "U$1") (pin "P$27") (pinfunction "GPA6_P$27") (pintype "bidirectional"))
    )
    (net (code "59") (name "Net-(D1-A9)") (class "Default")
      (node (ref "D1") (pin "10") (pinfunction "A9_10") (pintype "passive"))
      (node (ref "U$1") (pin "P$28") (pinfunction "GPA7_P$28") (pintype "bidirectional"))
    )
    (net (code "60") (name "Net-(D2-A)") (class "Default")
      (node (ref "D2") (pin "1") (pinfunction "A_1") (pintype "passive"))
      (node (ref "U$3") (pin "P$2") (pinfunction "GPB1_P$2") (pintype "bidirectional"))
    )
    (net (code "61") (name "Net-(D2-A1)") (class "Default")
      (node (ref "D2") (pin "2") (pinfunction "A1_2") (pintype "passive"))
      (node (ref "U$3") (pin "P$1") (pinfunction "GPB0_P$1") (pintype "bidirectional"))
    )
    (net (code "62") (name "Net-(D2-A2)") (class "Default")
      (node (ref "D2") (pin "3") (pinfunction "A2_3") (pintype "passive"))
      (node (ref "U$3") (pin "P$21") (pinfunction "GPA0_P$21") (pintype "bidirectional"))
    )
    (net (code "63") (name "Net-(D2-A3)") (class "Default")
      (node (ref "D2") (pin "4") (pinfunction "A3_4") (pintype "passive"))
      (node (ref "U$3") (pin "P$22") (pinfunction "GPA1_P$22") (pintype "bidirectional"))
    )
    (net (code "64") (name "Net-(D2-A4)") (class "Default")
      (node (ref "D2") (pin "5") (pinfunction "A4_5") (pintype "passive"))
      (node (ref "U$3") (pin "P$23") (pinfunction "GPA2_P$23") (pintype "bidirectional"))
    )
    (net (code "65") (name "Net-(D2-A5)") (class "Default")
      (node (ref "D2") (pin "6") (pinfunction "A5_6") (pintype "passive"))
      (node (ref "U$3") (pin "P$24") (pinfunction "GPA3_P$24") (pintype "bidirectional"))
    )
    (net (code "66") (name "Net-(D2-A6)") (class "Default")
      (node (ref "D2") (pin "7") (pinfunction "A6_7") (pintype "passive"))
      (node (ref "U$3") (pin "P$25") (pinfunction "GPA4_P$25") (pintype "bidirectional"))
    )
    (net (code "67") (name "Net-(D2-A7)") (class "Default")
      (node (ref "D2") (pin "8") (pinfunction "A7_8") (pintype "passive"))
      (node (ref "U$3") (pin "P$26") (pinfunction "GPA5_P$26") (pintype "bidirectional"))
    )
    (net (code "68") (name "Net-(D2-A8)") (class "Default")
      (node (ref "D2") (pin "9") (pinfunction "A8_9") (pintype "passive"))
      (node (ref "U$3") (pin "P$27") (pinfunction "GPA6_P$27") (pintype "bidirectional"))
    )
    (net (code "69") (name "Net-(D2-A9)") (class "Default")
      (node (ref "D2") (pin "10") (pinfunction "A9_10") (pintype "passive"))
      (node (ref "U$3") (pin "P$28") (pinfunction "GPA7_P$28") (pintype "bidirectional"))
    )
    (net (code "70") (name "Net-(LCD1-VO)") (class "Default")
      (node (ref "LCD1") (pin "3") (pinfunction "VO_3") (pintype "input"))
      (node (ref "R23") (pin "S") (pinfunction "S_S") (pintype "bidirectional"))
    )
    (net (code "71") (name "VDD_3P3V") (class "Default")
      (node (ref "D3") (pin "ANODE") (pinfunction "ANODE_ANODE") (pintype "bidirectional"))
      (node (ref "D4") (pin "ANODE") (pinfunction "ANODE_ANODE") (pintype "bidirectional"))
      (node (ref "R10") (pin "2") (pinfunction "2_2") (pintype "passive"))
      (node (ref "R11") (pin "2") (pinfunction "2_2") (pintype "passive"))
      (node (ref "R12") (pin "2") (pinfunction "2_2") (pintype "passive"))
      (node (ref "R13") (pin "2") (pinfunction "2_2") (pintype "passive"))
      (node (ref "R14") (pin "2") (pinfunction "2_2") (pintype "passive"))
      (node (ref "R15") (pin "2") (pinfunction "2_2") (pintype "passive"))
      (node (ref "R16") (pin "2") (pinfunction "2_2") (pintype "passive"))
      (node (ref "R17") (pin "2") (pinfunction "2_2") (pintype "passive"))
      (node (ref "R18") (pin "2") (pinfunction "2_2") (pintype "passive"))
      (node (ref "R19") (pin "1") (pinfunction "1_1") (pintype "passive"))
      (node (ref "R20") (pin "1") (pinfunction "1_1") (pintype "passive"))
      (node (ref "R21") (pin "1") (pinfunction "1_1") (pintype "passive"))
      (node (ref "R22") (pin "1") (pinfunction "1_1") (pintype "passive"))
      (node (ref "R4") (pin "2") (pinfunction "2_2") (pintype "passive"))
      (node (ref "R5") (pin "2") (pinfunction "2_2") (pintype "passive"))
      (node (ref "R6") (pin "2") (pinfunction "2_2") (pintype "passive"))
      (node (ref "R7") (pin "2") (pinfunction "2_2") (pintype "passive"))
      (node (ref "R8") (pin "2") (pinfunction "2_2") (pintype "passive"))
      (node (ref "R9") (pin "2") (pinfunction "2_2") (pintype "passive"))
      (node (ref "U1") (pin "P1_14") (pinfunction "3.3V_P1_14") (pintype "power_in"))
      (node (ref "U1") (pin "P2_23") (pinfunction "3.3V_P2_23") (pintype "power_in"))
    )
    (net (code "72") (name "VDD_5V") (class "Default")
      (node (ref "LCD1") (pin "15") (pinfunction "LEDA_15") (pintype "passive"))
      (node (ref "LCD1") (pin "2") (pinfunction "VCC_2") (pintype "power_in"))
      (node (ref "R23") (pin "CCW") (pinfunction "CCW_CCW") (pintype "passive"))
      (node (ref "U$1") (pin "P$9") (pinfunction "VDD_P$9") (pintype "bidirectional"))
      (node (ref "U$3") (pin "P$9") (pinfunction "VDD_P$9") (pintype "bidirectional"))
      (node (ref "U1") (pin "P1_24") (pinfunction "VOUT_P1_24") (pintype "power_in"))
      (node (ref "U1") (pin "P2_13") (pinfunction "VOUT_P2_13") (pintype "power_in"))
    )
    (net (code "73") (name "unconnected-(FUD1-PadP$1)") (class "Default")
      (node (ref "FUD1") (pin "P$1") (pinfunction "P$1_P$1") (pintype "no_connect"))
    )
    (net (code "74") (name "unconnected-(FUD2-PadP$1)") (class "Default")
      (node (ref "FUD2") (pin "P$1") (pinfunction "P$1_P$1") (pintype "no_connect"))
    )
    (net (code "75") (name "unconnected-(FUD5-PadP$1)") (class "Default")
      (node (ref "FUD5") (pin "P$1") (pinfunction "P$1_P$1") (pintype "no_connect"))
    )
    (net (code "76") (name "unconnected-(FUD6-PadP$1)") (class "Default")
      (node (ref "FUD6") (pin "P$1") (pinfunction "P$1_P$1") (pintype "no_connect"))
    )
    (net (code "77") (name "unconnected-(FUD9-PadP$1)") (class "Default")
      (node (ref "FUD9") (pin "P$1") (pinfunction "P$1_P$1") (pintype "no_connect"))
    )
    (net (code "78") (name "unconnected-(FUD10-PadP$1)") (class "Default")
      (node (ref "FUD10") (pin "P$1") (pinfunction "P$1_P$1") (pintype "no_connect"))
    )
    (net (code "79") (name "unconnected-(LCD1-R{slash}W-Pad5)") (class "Default")
      (node (ref "LCD1") (pin "5") (pinfunction "R/W_5") (pintype "input"))
    )
    (net (code "80") (name "unconnected-(S1-PadB)") (class "Default")
      (node (ref "S1") (pin "B") (pinfunction "B_B") (pintype "passive"))
    )
    (net (code "81") (name "unconnected-(S1-PadB1)") (class "Default")
      (node (ref "S1") (pin "B1") (pinfunction "B1_B1") (pintype "passive"))
    )
    (net (code "82") (name "unconnected-(S1-S-Pad3)") (class "Default")
      (node (ref "S1") (pin "3") (pinfunction "S_3") (pintype "passive"))
    )
    (net (code "83") (name "unconnected-(S2-PadB)") (class "Default")
      (node (ref "S2") (pin "B") (pinfunction "B_B") (pintype "passive"))
    )
    (net (code "84") (name "unconnected-(S2-PadB1)") (class "Default")
      (node (ref "S2") (pin "B1") (pinfunction "B1_B1") (pintype "passive"))
    )
    (net (code "85") (name "unconnected-(S2-S-Pad3)") (class "Default")
      (node (ref "S2") (pin "3") (pinfunction "S_3") (pintype "passive"))
    )
    (net (code "86") (name "unconnected-(S3-PadB)") (class "Default")
      (node (ref "S3") (pin "B") (pinfunction "B_B") (pintype "passive"))
    )
    (net (code "87") (name "unconnected-(S3-PadB1)") (class "Default")
      (node (ref "S3") (pin "B1") (pinfunction "B1_B1") (pintype "passive"))
    )
    (net (code "88") (name "unconnected-(S3-S-Pad3)") (class "Default")
      (node (ref "S3") (pin "3") (pinfunction "S_3") (pintype "passive"))
    )
    (net (code "89") (name "unconnected-(S4-PadB)") (class "Default")
      (node (ref "S4") (pin "B") (pinfunction "B_B") (pintype "passive"))
    )
    (net (code "90") (name "unconnected-(S4-PadB1)") (class "Default")
      (node (ref "S4") (pin "B1") (pinfunction "B1_B1") (pintype "passive"))
    )
    (net (code "91") (name "unconnected-(S4-S-Pad3)") (class "Default")
      (node (ref "S4") (pin "3") (pinfunction "S_3") (pintype "passive"))
    )
    (net (code "92") (name "unconnected-(S5-PadB)") (class "Default")
      (node (ref "S5") (pin "B") (pinfunction "B_B") (pintype "passive"))
    )
    (net (code "93") (name "unconnected-(S5-PadB1)") (class "Default")
      (node (ref "S5") (pin "B1") (pinfunction "B1_B1") (pintype "passive"))
    )
    (net (code "94") (name "unconnected-(S5-S-Pad3)") (class "Default")
      (node (ref "S5") (pin "3") (pinfunction "S_3") (pintype "passive"))
    )
    (net (code "95") (name "unconnected-(S6-PadB)") (class "Default")
      (node (ref "S6") (pin "B") (pinfunction "B_B") (pintype "passive"))
    )
    (net (code "96") (name "unconnected-(S6-PadB1)") (class "Default")
      (node (ref "S6") (pin "B1") (pinfunction "B1_B1") (pintype "passive"))
    )
    (net (code "97") (name "unconnected-(S6-S-Pad3)") (class "Default")
      (node (ref "S6") (pin "3") (pinfunction "S_3") (pintype "passive"))
    )
    (net (code "98") (name "unconnected-(S7-PadB)") (class "Default")
      (node (ref "S7") (pin "B") (pinfunction "B_B") (pintype "passive"))
    )
    (net (code "99") (name "unconnected-(S7-PadB1)") (class "Default")
      (node (ref "S7") (pin "B1") (pinfunction "B1_B1") (pintype "passive"))
    )
    (net (code "100") (name "unconnected-(S7-S-Pad3)") (class "Default")
      (node (ref "S7") (pin "3") (pinfunction "S_3") (pintype "passive"))
    )
    (net (code "101") (name "unconnected-(S8-PadB)") (class "Default")
      (node (ref "S8") (pin "B") (pinfunction "B_B") (pintype "passive"))
    )
    (net (code "102") (name "unconnected-(S8-PadB1)") (class "Default")
      (node (ref "S8") (pin "B1") (pinfunction "B1_B1") (pintype "passive"))
    )
    (net (code "103") (name "unconnected-(S8-S-Pad3)") (class "Default")
      (node (ref "S8") (pin "3") (pinfunction "S_3") (pintype "passive"))
    )
    (net (code "104") (name "unconnected-(S9-PadB)") (class "Default")
      (node (ref "S9") (pin "B") (pinfunction "B_B") (pintype "passive"))
    )
    (net (code "105") (name "unconnected-(S9-PadB1)") (class "Default")
      (node (ref "S9") (pin "B1") (pinfunction "B1_B1") (pintype "passive"))
    )
    (net (code "106") (name "unconnected-(S9-S-Pad3)") (class "Default")
      (node (ref "S9") (pin "3") (pinfunction "S_3") (pintype "passive"))
    )
    (net (code "107") (name "unconnected-(S10-PadB)") (class "Default")
      (node (ref "S10") (pin "B") (pinfunction "B_B") (pintype "passive"))
    )
    (net (code "108") (name "unconnected-(S10-PadB1)") (class "Default")
      (node (ref "S10") (pin "B1") (pinfunction "B1_B1") (pintype "passive"))
    )
    (net (code "109") (name "unconnected-(S10-S-Pad3)") (class "Default")
      (node (ref "S10") (pin "3") (pinfunction "S_3") (pintype "passive"))
    )
    (net (code "110") (name "unconnected-(S11-PadB)") (class "Default")
      (node (ref "S11") (pin "B") (pinfunction "B_B") (pintype "passive"))
    )
    (net (code "111") (name "unconnected-(S11-PadB1)") (class "Default")
      (node (ref "S11") (pin "B1") (pinfunction "B1_B1") (pintype "passive"))
    )
    (net (code "112") (name "unconnected-(S11-S-Pad3)") (class "Default")
      (node (ref "S11") (pin "3") (pinfunction "S_3") (pintype "passive"))
    )
    (net (code "113") (name "unconnected-(S12-PadB)") (class "Default")
      (node (ref "S12") (pin "B") (pinfunction "B_B") (pintype "passive"))
    )
    (net (code "114") (name "unconnected-(S12-PadB1)") (class "Default")
      (node (ref "S12") (pin "B1") (pinfunction "B1_B1") (pintype "passive"))
    )
    (net (code "115") (name "unconnected-(S12-S-Pad3)") (class "Default")
      (node (ref "S12") (pin "3") (pinfunction "S_3") (pintype "passive"))
    )
    (net (code "116") (name "unconnected-(S13-PadB)") (class "Default")
      (node (ref "S13") (pin "B") (pinfunction "B_B") (pintype "passive"))
    )
    (net (code "117") (name "unconnected-(S13-PadB1)") (class "Default")
      (node (ref "S13") (pin "B1") (pinfunction "B1_B1") (pintype "passive"))
    )
    (net (code "118") (name "unconnected-(S13-S-Pad3)") (class "Default")
      (node (ref "S13") (pin "3") (pinfunction "S_3") (pintype "passive"))
    )
    (net (code "119") (name "unconnected-(S14-PadB)") (class "Default")
      (node (ref "S14") (pin "B") (pinfunction "B_B") (pintype "passive"))
    )
    (net (code "120") (name "unconnected-(S14-PadB1)") (class "Default")
      (node (ref "S14") (pin "B1") (pinfunction "B1_B1") (pintype "passive"))
    )
    (net (code "121") (name "unconnected-(S14-S-Pad3)") (class "Default")
      (node (ref "S14") (pin "3") (pinfunction "S_3") (pintype "passive"))
    )
    (net (code "122") (name "unconnected-(S15-PadB)") (class "Default")
      (node (ref "S15") (pin "B") (pinfunction "B_B") (pintype "passive"))
    )
    (net (code "123") (name "unconnected-(S15-PadB1)") (class "Default")
      (node (ref "S15") (pin "B1") (pinfunction "B1_B1") (pintype "passive"))
    )
    (net (code "124") (name "unconnected-(S15-S-Pad3)") (class "Default")
      (node (ref "S15") (pin "3") (pinfunction "S_3") (pintype "passive"))
    )
    (net (code "125") (name "unconnected-(SW1-Pad2)") (class "Default")
      (node (ref "SW1") (pin "2") (pinfunction "2_2") (pintype "bidirectional"))
    )
    (net (code "126") (name "unconnected-(SW1-Pad4)") (class "Default")
      (node (ref "SW1") (pin "4") (pinfunction "4_4") (pintype "bidirectional"))
    )
    (net (code "127") (name "unconnected-(SW2-Pad2)") (class "Default")
      (node (ref "SW2") (pin "2") (pinfunction "2_2") (pintype "bidirectional"))
    )
    (net (code "128") (name "unconnected-(SW2-Pad4)") (class "Default")
      (node (ref "SW2") (pin "4") (pinfunction "4_4") (pintype "bidirectional"))
    )
    (net (code "129") (name "unconnected-(SW3-Pad2)") (class "Default")
      (node (ref "SW3") (pin "2") (pinfunction "2_2") (pintype "bidirectional"))
    )
    (net (code "130") (name "unconnected-(SW3-Pad4)") (class "Default")
      (node (ref "SW3") (pin "4") (pinfunction "4_4") (pintype "bidirectional"))
    )
    (net (code "131") (name "unconnected-(SW4-Pad2)") (class "Default")
      (node (ref "SW4") (pin "2") (pinfunction "2_2") (pintype "bidirectional"))
    )
    (net (code "132") (name "unconnected-(SW4-Pad4)") (class "Default")
      (node (ref "SW4") (pin "4") (pinfunction "4_4") (pintype "bidirectional"))
    )
    (net (code "133") (name "unconnected-(U$1-A0-PadP$15)") (class "Default")
      (node (ref "U$1") (pin "P$15") (pinfunction "A0_P$15") (pintype "bidirectional"))
    )
    (net (code "134") (name "unconnected-(U$1-A1-PadP$16)") (class "Default")
      (node (ref "U$1") (pin "P$16") (pinfunction "A1_P$16") (pintype "bidirectional"))
    )
    (net (code "135") (name "unconnected-(U$1-A2-PadP$17)") (class "Default")
      (node (ref "U$1") (pin "P$17") (pinfunction "A2_P$17") (pintype "bidirectional"))
    )
    (net (code "136") (name "unconnected-(U$1-GPB2-PadP$3)") (class "Default")
      (node (ref "U$1") (pin "P$3") (pinfunction "GPB2_P$3") (pintype "bidirectional"))
    )
    (net (code "137") (name "unconnected-(U$1-GPB3-PadP$4)") (class "Default")
      (node (ref "U$1") (pin "P$4") (pinfunction "GPB3_P$4") (pintype "bidirectional"))
    )
    (net (code "138") (name "unconnected-(U$1-GPB4-PadP$5)") (class "Default")
      (node (ref "U$1") (pin "P$5") (pinfunction "GPB4_P$5") (pintype "bidirectional"))
    )
    (net (code "139") (name "unconnected-(U$1-GPB5-PadP$6)") (class "Default")
      (node (ref "U$1") (pin "P$6") (pinfunction "GPB5_P$6") (pintype "bidirectional"))
    )
    (net (code "140") (name "unconnected-(U$1-GPB6-PadP$7)") (class "Default")
      (node (ref "U$1") (pin "P$7") (pinfunction "GPB6_P$7") (pintype "bidirectional"))
    )
    (net (code "141") (name "unconnected-(U$1-GPB7-PadP$8)") (class "Default")
      (node (ref "U$1") (pin "P$8") (pinfunction "GPB7_P$8") (pintype "bidirectional"))
    )
    (net (code "142") (name "unconnected-(U$1-INTA-PadP$20)") (class "Default")
      (node (ref "U$1") (pin "P$20") (pinfunction "INTA_P$20") (pintype "bidirectional"))
    )
    (net (code "143") (name "unconnected-(U$1-INTB-PadP$19)") (class "Default")
      (node (ref "U$1") (pin "P$19") (pinfunction "INTB_P$19") (pintype "bidirectional"))
    )
    (net (code "144") (name "unconnected-(U$1-NC-11-PadP$11)") (class "Default")
      (node (ref "U$1") (pin "P$11") (pinfunction "NC-11_P$11") (pintype "bidirectional"))
    )
    (net (code "145") (name "unconnected-(U$1-NC-14-PadP$14)") (class "Default")
      (node (ref "U$1") (pin "P$14") (pinfunction "NC-14_P$14") (pintype "bidirectional"))
    )
    (net (code "146") (name "unconnected-(U$1-RESET-PadP$18)") (class "Default")
      (node (ref "U$1") (pin "P$18") (pinfunction "RESET_P$18") (pintype "bidirectional"))
    )
    (net (code "147") (name "unconnected-(U$3-A0-PadP$15)") (class "Default")
      (node (ref "U$3") (pin "P$15") (pinfunction "A0_P$15") (pintype "bidirectional"))
    )
    (net (code "148") (name "unconnected-(U$3-A1-PadP$16)") (class "Default")
      (node (ref "U$3") (pin "P$16") (pinfunction "A1_P$16") (pintype "bidirectional"))
    )
    (net (code "149") (name "unconnected-(U$3-A2-PadP$17)") (class "Default")
      (node (ref "U$3") (pin "P$17") (pinfunction "A2_P$17") (pintype "bidirectional"))
    )
    (net (code "150") (name "unconnected-(U$3-GPB2-PadP$3)") (class "Default")
      (node (ref "U$3") (pin "P$3") (pinfunction "GPB2_P$3") (pintype "bidirectional"))
    )
    (net (code "151") (name "unconnected-(U$3-GPB3-PadP$4)") (class "Default")
      (node (ref "U$3") (pin "P$4") (pinfunction "GPB3_P$4") (pintype "bidirectional"))
    )
    (net (code "152") (name "unconnected-(U$3-GPB4-PadP$5)") (class "Default")
      (node (ref "U$3") (pin "P$5") (pinfunction "GPB4_P$5") (pintype "bidirectional"))
    )
    (net (code "153") (name "unconnected-(U$3-GPB5-PadP$6)") (class "Default")
      (node (ref "U$3") (pin "P$6") (pinfunction "GPB5_P$6") (pintype "bidirectional"))
    )
    (net (code "154") (name "unconnected-(U$3-GPB6-PadP$7)") (class "Default")
      (node (ref "U$3") (pin "P$7") (pinfunction "GPB6_P$7") (pintype "bidirectional"))
    )
    (net (code "155") (name "unconnected-(U$3-GPB7-PadP$8)") (class "Default")
      (node (ref "U$3") (pin "P$8") (pinfunction "GPB7_P$8") (pintype "bidirectional"))
    )
    (net (code "156") (name "unconnected-(U$3-INTA-PadP$20)") (class "Default")
      (node (ref "U$3") (pin "P$20") (pinfunction "INTA_P$20") (pintype "bidirectional"))
    )
    (net (code "157") (name "unconnected-(U$3-INTB-PadP$19)") (class "Default")
      (node (ref "U$3") (pin "P$19") (pinfunction "INTB_P$19") (pintype "bidirectional"))
    )
    (net (code "158") (name "unconnected-(U$3-NC-11-PadP$11)") (class "Default")
      (node (ref "U$3") (pin "P$11") (pinfunction "NC-11_P$11") (pintype "bidirectional"))
    )
    (net (code "159") (name "unconnected-(U$3-NC-14-PadP$14)") (class "Default")
      (node (ref "U$3") (pin "P$14") (pinfunction "NC-14_P$14") (pintype "bidirectional"))
    )
    (net (code "160") (name "unconnected-(U$3-RESET-PadP$18)") (class "Default")
      (node (ref "U$3") (pin "P$18") (pinfunction "RESET_P$18") (pintype "bidirectional"))
    )
    (net (code "161") (name "unconnected-(U1-AIN5(3.3V)GPIO86-PadP2_35)") (class "Default")
      (node (ref "U1") (pin "P2_35") (pinfunction "AIN5(3.3V)GPIO86_P2_35") (pintype "bidirectional"))
    )
    (net (code "162") (name "unconnected-(U1-BAT.TEMP-PadP2_16)") (class "Default")
      (node (ref "U1") (pin "P2_16") (pinfunction "BAT.TEMP_P2_16") (pintype "input"))
    )
    (net (code "163") (name "unconnected-(U1-DRVVBUS-PadP1_03)") (class "Default")
      (node (ref "U1") (pin "P1_03") (pinfunction "DRVVBUS_P1_03") (pintype "bidirectional"))
    )
    (net (code "164") (name "unconnected-(U1-GND-PadP1_15)") (class "Default")
      (node (ref "U1") (pin "P1_15") (pinfunction "GND_P1_15") (pintype "bidirectional"))
    )
    (net (code "165") (name "unconnected-(U1-GPIO20-PadP1_20)") (class "Default")
      (node (ref "U1") (pin "P1_20") (pinfunction "GPIO20_P1_20") (pintype "bidirectional"))
    )
    (net (code "166") (name "unconnected-(U1-GPIO23-PadP2_03)") (class "Default")
      (node (ref "U1") (pin "P2_03") (pinfunction "GPIO23_P2_03") (pintype "bidirectional"))
    )
    (net (code "167") (name "unconnected-(U1-PRU0.1-PadP1_33)") (class "Default")
      (node (ref "U1") (pin "P1_33") (pinfunction "PRU0.1_P1_33") (pintype "bidirectional"))
    )
    (net (code "168") (name "unconnected-(U1-PWM0A-PadP1_36)") (class "Default")
      (node (ref "U1") (pin "P1_36") (pinfunction "PWM0A_P1_36") (pintype "bidirectional"))
    )
    (net (code "169") (name "unconnected-(U1-PWM1A-PadP2_01)") (class "Default")
      (node (ref "U1") (pin "P2_01") (pinfunction "PWM1A_P2_01") (pintype "bidirectional"))
    )
    (net (code "170") (name "unconnected-(U1-PWR.BTN-PadP2_12)") (class "Default")
      (node (ref "U1") (pin "P2_12") (pinfunction "PWR.BTN_P2_12") (pintype "input"))
    )
    (net (code "171") (name "unconnected-(U1-RESET#-PadP2_26)") (class "Default")
      (node (ref "U1") (pin "P2_26") (pinfunction "RESET#_P2_26") (pintype "input"))
    )
    (net (code "172") (name "unconnected-(U1-UART0.RX-PadP1_32)") (class "Default")
      (node (ref "U1") (pin "P1_32") (pinfunction "UART0.RX_P1_32") (pintype "bidirectional"))
    )
    (net (code "173") (name "unconnected-(U1-UART0.TX-PadP1_30)") (class "Default")
      (node (ref "U1") (pin "P1_30") (pinfunction "UART0.TX_P1_30") (pintype "bidirectional"))
    )
    (net (code "174") (name "unconnected-(U1-UART4.RX-PadP2_05)") (class "Default")
      (node (ref "U1") (pin "P2_05") (pinfunction "UART4.RX_P2_05") (pintype "bidirectional"))
    )
    (net (code "175") (name "unconnected-(U1-UART4.TX-PadP2_07)") (class "Default")
      (node (ref "U1") (pin "P2_07") (pinfunction "UART4.TX_P2_07") (pintype "bidirectional"))
    )
    (net (code "176") (name "unconnected-(U1-USB1.D+-PadP1_11)") (class "Default")
      (node (ref "U1") (pin "P1_11") (pinfunction "USB1.D+_P1_11") (pintype "bidirectional"))
    )
    (net (code "177") (name "unconnected-(U1-USB1.D--PadP1_09)") (class "Default")
      (node (ref "U1") (pin "P1_09") (pinfunction "USB1.D-_P1_09") (pintype "bidirectional"))
    )
    (net (code "178") (name "unconnected-(U1-USB1.ID-PadP1_13)") (class "Default")
      (node (ref "U1") (pin "P1_13") (pinfunction "USB1.ID_P1_13") (pintype "bidirectional"))
    )
    (net (code "179") (name "unconnected-(U1-USB1.VIN-PadP1_07)") (class "Default")
      (node (ref "U1") (pin "P1_07") (pinfunction "USB1.VIN_P1_07") (pintype "bidirectional"))
    )
    (net (code "180") (name "unconnected-(U1-VBUS-PadP1_05)") (class "Default")
      (node (ref "U1") (pin "P1_05") (pinfunction "VBUS_P1_05") (pintype "bidirectional"))
    )
  )
)
